# 04_-BUTTON.net
KiCad netlist of a schematic drawn in Altium Designer
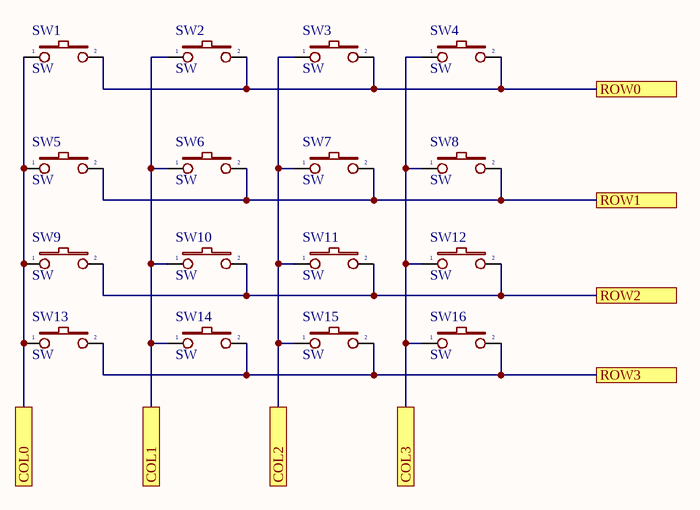
[diagram p0: [04]-BUTTON.SchDoc]

(export (version "E")
  (design (tool "Eeschema 10.0.6"))
  (components
    (comp (ref "SW1")
      (value "SW")
      (footprint "SW-SMD")
      (description "Switch button 2 pin")
      (libsource (lib "My Library") (part "SW2"))
    )
    (comp (ref "SW2")
      (value "SW")
      (footprint "SW-SMD")
      (description "Switch button 2 pin")
      (libsource (lib "My Library") (part "SW2"))
    )
    (comp (ref "SW3")
      (value "SW")
      (footprint "SW-SMD")
      (description "Switch button 2 pin")
      (libsource (lib "My Library") (part "SW2"))
    )
    (comp (ref "SW4")
      (value "SW")
      (footprint "SW-SMD")
      (description "Switch button 2 pin")
      (libsource (lib "My Library") (part "SW2"))
    )
    (comp (ref "SW5")
      (value "SW")
      (footprint "SW-SMD")
      (description "Switch button 2 pin")
      (libsource (lib "My Library") (part "SW2"))
    )
    (comp (ref "SW6")
      (value "SW")
      (footprint "SW-SMD")
      (description "Switch button 2 pin")
      (libsource (lib "My Library") (part "SW2"))
    )
    (comp (ref "SW7")
      (value "SW")
      (footprint "SW-SMD")
      (description "Switch button 2 pin")
      (libsource (lib "My Library") (part "SW2"))
    )
    (comp (ref "SW8")
      (value "SW")
      (footprint "SW-SMD")
      (description "Switch button 2 pin")
      (libsource (lib "My Library") (part "SW2"))
    )
    (comp (ref "SW9")
      (value "SW")
      (footprint "SW-SMD")
      (description "Switch button 2 pin")
      (libsource (lib "My Library") (part "SW2"))
    )
    (comp (ref "SW10")
      (value "SW")
      (footprint "SW-SMD")
      (description "Switch button 2 pin")
      (libsource (lib "My Library") (part "SW2"))
    )
    (comp (ref "SW11")
      (value "SW")
      (footprint "SW-SMD")
      (description "Switch button 2 pin")
      (libsource (lib "My Library") (part "SW2"))
    )
    (comp (ref "SW12")
      (value "SW")
      (footprint "SW-SMD")
      (description "Switch button 2 pin")
      (libsource (lib "My Library") (part "SW2"))
    )
    (comp (ref "SW13")
      (value "SW")
      (footprint "SW-SMD")
      (description "Switch button 2 pin")
      (libsource (lib "My Library") (part "SW2"))
    )
    (comp (ref "SW14")
      (value "SW")
      (footprint "SW-SMD")
      (description "Switch button 2 pin")
      (libsource (lib "My Library") (part "SW2"))
    )
    (comp (ref "SW15")
      (value "SW")
      (footprint "SW-SMD")
      (description "Switch button 2 pin")
      (libsource (lib "My Library") (part "SW2"))
    )
    (comp (ref "SW16")
      (value "SW")
      (footprint "SW-SMD")
      (description "Switch button 2 pin")
      (libsource (lib "My Library") (part "SW2"))
    )
  )
  (nets
    (net (code "1") (name "/COL0") (class "Default")
      (node (ref "SW1") (pin "1") (pinfunction "1_1") (pintype "passive"))
      (node (ref "SW13") (pin "1") (pinfunction "1_1") (pintype "passive"))
      (node (ref "SW5") (pin "1") (pinfunction "1_1") (pintype "passive"))
      (node (ref "SW9") (pin "1") (pinfunction "1_1") (pintype "passive"))
    )
    (net (code "2") (name "/COL1") (class "Default")
      (node (ref "SW10") (pin "1") (pinfunction "1_1") (pintype "passive"))
      (node (ref "SW14") (pin "1") (pinfunction "1_1") (pintype "passive"))
      (node (ref "SW2") (pin "1") (pinfunction "1_1") (pintype "passive"))
      (node (ref "SW6") (pin "1") (pinfunction "1_1") (pintype "passive"))
    )
    (net (code "3") (name "/COL2") (class "Default")
      (node (ref "SW11") (pin "1") (pinfunction "1_1") (pintype "passive"))
      (node (ref "SW15") (pin "1") (pinfunction "1_1") (pintype "passive"))
      (node (ref "SW3") (pin "1") (pinfunction "1_1") (pintype "passive"))
      (node (ref "SW7") (pin "1") (pinfunction "1_1") (pintype "passive"))
    )
    (net (code "4") (name "/COL3") (class "Default")
      (node (ref "SW12") (pin "1") (pinfunction "1_1") (pintype "passive"))
      (node (ref "SW16") (pin "1") (pinfunction "1_1") (pintype "passive"))
      (node (ref "SW4") (pin "1") (pinfunction "1_1") (pintype "passive"))
      (node (ref "SW8") (pin "1") (pinfunction "1_1") (pintype "passive"))
    )
    (net (code "5") (name "/ROW0") (class "Default")
      (node (ref "SW1") (pin "2") (pinfunction "2_2") (pintype "passive"))
      (node (ref "SW2") (pin "2") (pinfunction "2_2") (pintype "passive"))
      (node (ref "SW3") (pin "2") (pinfunction "2_2") (pintype "passive"))
      (node (ref "SW4") (pin "2") (pinfunction "2_2") (pintype "passive"))
    )
    (net (code "6") (name "/ROW1") (class "Default")
      (node (ref "SW5") (pin "2") (pinfunction "2_2") (pintype "passive"))
      (node (ref "SW6") (pin "2") (pinfunction "2_2") (pintype "passive"))
      (node (ref "SW7") (pin "2") (pinfunction "2_2") (pintype "passive"))
      (node (ref "SW8") (pin "2") (pinfunction "2_2") (pintype "passive"))
    )
    (net (code "7") (name "/ROW2") (class "Default")
      (node (ref "SW10") (pin "2") (pinfunction "2_2") (pintype "passive"))
      (node (ref "SW11") (pin "2") (pinfunction "2_2") (pintype "passive"))
      (node (ref "SW12") (pin "2") (pinfunction "2_2") (pintype "passive"))
      (node (ref "SW9") (pin "2") (pinfunction "2_2") (pintype "passive"))
    )
    (net (code "8") (name "/ROW3") (class "Default")
      (node (ref "SW13") (pin "2") (pinfunction "2_2") (pintype "passive"))
      (node (ref "SW14") (pin "2") (pinfunction "2_2") (pintype "passive"))
      (node (ref "SW15") (pin "2") (pinfunction "2_2") (pintype "passive"))
      (node (ref "SW16") (pin "2") (pinfunction "2_2") (pintype "passive"))
    )
  )
)
